# SparkFun_6DoF_ISM330DHCX.net
KiCad netlist of a schematic drawn in EAGLE
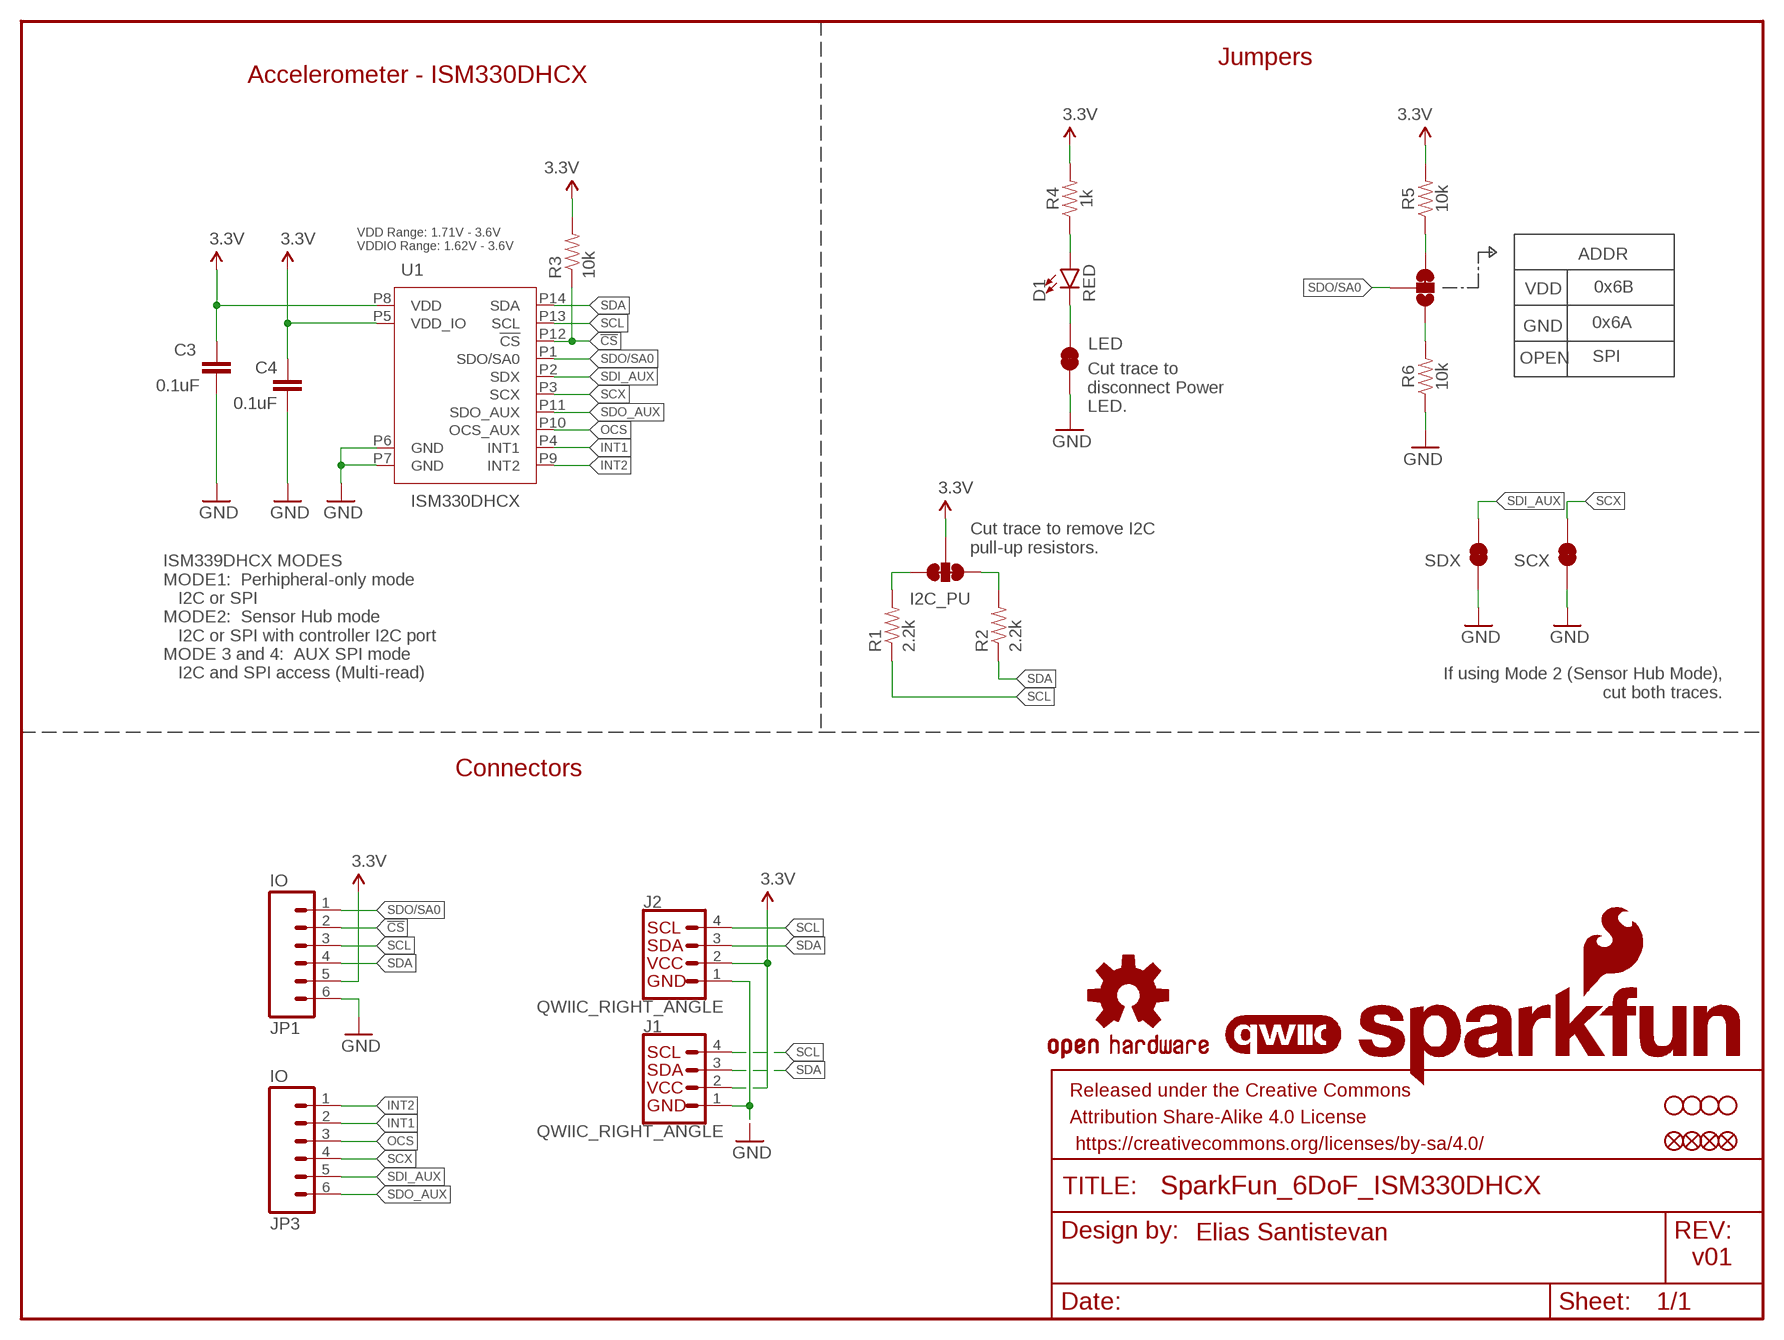
[diagram p0: schematic, sheet 1]

(export (version "E")
  (design (tool "Eeschema 10.0.6"))
  (components
    (comp (ref "ADDR")
      (value "JUMPER-SMT_3_1-NC_TRACE_SILK")
      (footprint "eagle-import:SMT-JUMPER_3_1-NC_TRACE_SILK")
      (libsource (lib "eagle-import") (part "JUMPER-SMT_3_1-NC_TRACE_SILK"))
    )
    (comp (ref "C3")
      (value "0.1uF")
      (footprint "eagle-import:0603")
      (libsource (lib "eagle-import") (part "0.1UF-0603-25V-(+80/-20%)"))
    )
    (comp (ref "C4")
      (value "0.1uF")
      (footprint "eagle-import:0603")
      (libsource (lib "eagle-import") (part "0.1UF-0603-25V-(+80/-20%)"))
    )
    (comp (ref "D1")
      (value "RED")
      (footprint "eagle-import:LED-0603")
      (libsource (lib "eagle-import") (part "LED-RED0603"))
    )
    (comp (ref "FD1")
      (value "FIDUCIALUFIDUCIAL")
      (footprint "eagle-import:FIDUCIAL-MICRO")
      (libsource (lib "eagle-import") (part "FIDUCIALUFIDUCIAL"))
    )
    (comp (ref "FD2")
      (value "FIDUCIALUFIDUCIAL")
      (footprint "eagle-import:FIDUCIAL-MICRO")
      (libsource (lib "eagle-import") (part "FIDUCIALUFIDUCIAL"))
    )
    (comp (ref "FID1")
      (value "FIDUCIALUFIDUCIAL")
      (footprint "eagle-import:FIDUCIAL-MICRO")
      (libsource (lib "eagle-import") (part "FIDUCIALUFIDUCIAL"))
    )
    (comp (ref "FID2")
      (value "FIDUCIALUFIDUCIAL")
      (footprint "eagle-import:FIDUCIAL-MICRO")
      (libsource (lib "eagle-import") (part "FIDUCIALUFIDUCIAL"))
    )
    (comp (ref "FRAME1")
      (value "FRAME-LETTER")
      (footprint "eagle-import:CREATIVE_COMMONS")
      (fields (field (name "DESIGNER") "Elias Santistevan"))
      (libsource (lib "eagle-import") (part "FRAME-LETTER"))
    )
    (comp (ref "I2C_PU")
      (value "S_MODE")
      (footprint "eagle-import:SMT-JUMPER_3_2-NC_TRACE_SILK")
      (libsource (lib "eagle-import") (part "JUMPER-SMT_3_2-NC_TRACE_SILK"))
    )
    (comp (ref "J1")
      (value "QWIIC_RIGHT_ANGLE")
      (footprint "eagle-import:JST04_1MM_RA")
      (libsource (lib "eagle-import") (part "QWIIC_CONNECTORJS-1MM"))
    )
    (comp (ref "J2")
      (value "QWIIC_RIGHT_ANGLE")
      (footprint "eagle-import:JST04_1MM_RA")
      (libsource (lib "eagle-import") (part "QWIIC_CONNECTORJS-1MM"))
    )
    (comp (ref "JP1")
      (value "IO")
      (footprint "eagle-import:1X06_NO_SILK")
      (libsource (lib "eagle-import") (part "CONN_06NO_SILK_NO_POP"))
    )
    (comp (ref "JP3")
      (value "IO")
      (footprint "eagle-import:1X06_NO_SILK")
      (libsource (lib "eagle-import") (part "CONN_06NO_SILK_NO_POP"))
    )
    (comp (ref "LED")
      (value "JUMPER-SMT_2_NC_TRACE_SILK")
      (footprint "eagle-import:SMT-JUMPER_2_NC_TRACE_SILK")
      (libsource (lib "eagle-import") (part "JUMPER-SMT_2_NC_TRACE_SILK"))
    )
    (comp (ref "LOGO1")
      (value "QWIIC_LOGO_4MM")
      (footprint "eagle-import:QWIIC_4MM")
      (libsource (lib "eagle-import") (part "QWIIC_LOGO_4MM"))
    )
    (comp (ref "LOGO2")
      (value "OSHW-LOGOMINI")
      (footprint "eagle-import:OSHW-LOGO-MINI")
      (libsource (lib "eagle-import") (part "OSHW-LOGOMINI"))
    )
    (comp (ref "LOGO3")
      (value "SFE_LOGO_NAME_FLAME.1_INCH")
      (footprint "eagle-import:SFE_LOGO_NAME_FLAME_.1")
      (libsource (lib "eagle-import") (part "SFE_LOGO_NAME_FLAME.1_INCH"))
    )
    (comp (ref "R1")
      (value "2.2k")
      (footprint "eagle-import:0603")
      (libsource (lib "eagle-import") (part "2.2KOHM-0603-1/10W-1%"))
    )
    (comp (ref "R2")
      (value "2.2k")
      (footprint "eagle-import:0603")
      (libsource (lib "eagle-import") (part "2.2KOHM-0603-1/10W-1%"))
    )
    (comp (ref "R3")
      (value "10k")
      (footprint "eagle-import:0603")
      (libsource (lib "eagle-import") (part "10KOHM-0603-1/10W-1%"))
    )
    (comp (ref "R4")
      (value "1k")
      (footprint "eagle-import:0603")
      (libsource (lib "eagle-import") (part "1KOHM-0603-1/10W-1%"))
    )
    (comp (ref "R5")
      (value "10k")
      (footprint "eagle-import:0603")
      (libsource (lib "eagle-import") (part "10KOHM-0603-1/10W-1%"))
    )
    (comp (ref "R6")
      (value "10k")
      (footprint "eagle-import:0603")
      (libsource (lib "eagle-import") (part "10KOHM-0603-1/10W-1%"))
    )
    (comp (ref "SCX")
      (value "JUMPER-SMT_2_NC_TRACE_SILK")
      (footprint "eagle-import:SMT-JUMPER_2_NC_TRACE_SILK")
      (libsource (lib "eagle-import") (part "JUMPER-SMT_2_NC_TRACE_SILK"))
    )
    (comp (ref "SDX")
      (value "JUMPER-SMT_2_NC_TRACE_SILK")
      (footprint "eagle-import:SMT-JUMPER_2_NC_TRACE_SILK")
      (libsource (lib "eagle-import") (part "JUMPER-SMT_2_NC_TRACE_SILK"))
    )
    (comp (ref "STANDOFF1")
      (value "STAND-OFFTIGHT")
      (footprint "eagle-import:STAND-OFF-TIGHT")
      (libsource (lib "eagle-import") (part "STAND-OFFTIGHT"))
    )
    (comp (ref "STANDOFF2")
      (value "STAND-OFFTIGHT")
      (footprint "eagle-import:STAND-OFF-TIGHT")
      (libsource (lib "eagle-import") (part "STAND-OFFTIGHT"))
    )
    (comp (ref "STANDOFF3")
      (value "STAND-OFFTIGHT")
      (footprint "eagle-import:STAND-OFF-TIGHT")
      (libsource (lib "eagle-import") (part "STAND-OFFTIGHT"))
    )
    (comp (ref "STANDOFF4")
      (value "STAND-OFFTIGHT")
      (footprint "eagle-import:STAND-OFF-TIGHT")
      (libsource (lib "eagle-import") (part "STAND-OFFTIGHT"))
    )
    (comp (ref "U1")
      (value "ISM330DHCX")
      (footprint "eagle-import:LGA-14L")
      (libsource (lib "eagle-import") (part "ISM330DHCX"))
    )
  )
  (nets
    (net (code "1") (name "/~{CS}") (class "Default")
      (node (ref "JP1") (pin "2") (pinfunction "2_2") (pintype "passive"))
      (node (ref "R3") (pin "1") (pinfunction "1_1") (pintype "passive"))
      (node (ref "U1") (pin "P12") (pinfunction "~{CS}_P12") (pintype "bidirectional"))
    )
    (net (code "2") (name "3.3V") (class "Default")
      (node (ref "C3") (pin "1") (pinfunction "1_1") (pintype "passive"))
      (node (ref "C4") (pin "1") (pinfunction "1_1") (pintype "passive"))
      (node (ref "I2C_PU") (pin "2") (pinfunction "2_2") (pintype "passive"))
      (node (ref "J1") (pin "2") (pinfunction "2_2") (pintype "power_in"))
      (node (ref "J2") (pin "2") (pinfunction "2_2") (pintype "power_in"))
      (node (ref "JP1") (pin "5") (pinfunction "5_5") (pintype "passive"))
      (node (ref "R3") (pin "2") (pinfunction "2_2") (pintype "passive"))
      (node (ref "R4") (pin "2") (pinfunction "2_2") (pintype "passive"))
      (node (ref "R5") (pin "2") (pinfunction "2_2") (pintype "passive"))
      (node (ref "U1") (pin "P5") (pinfunction "VDD_IO_P5") (pintype "power_in"))
      (node (ref "U1") (pin "P8") (pinfunction "VDD_P8") (pintype "power_in"))
    )
    (net (code "3") (name "GND") (class "Default")
      (node (ref "C3") (pin "2") (pinfunction "2_2") (pintype "passive"))
      (node (ref "C4") (pin "2") (pinfunction "2_2") (pintype "passive"))
      (node (ref "J1") (pin "1") (pinfunction "1_1") (pintype "power_in"))
      (node (ref "J2") (pin "1") (pinfunction "1_1") (pintype "power_in"))
      (node (ref "JP1") (pin "6") (pinfunction "6_6") (pintype "passive"))
      (node (ref "LED") (pin "1") (pinfunction "1_1") (pintype "passive"))
      (node (ref "R6") (pin "1") (pinfunction "1_1") (pintype "passive"))
      (node (ref "SCX") (pin "1") (pinfunction "1_1") (pintype "passive"))
      (node (ref "SDX") (pin "1") (pinfunction "1_1") (pintype "passive"))
      (node (ref "U1") (pin "P6") (pinfunction "GND_P6") (pintype "power_in"))
      (node (ref "U1") (pin "P7") (pinfunction "GND_P7") (pintype "power_in"))
    )
    (net (code "4") (name "INT1") (class "Default")
      (node (ref "JP3") (pin "2") (pinfunction "2_2") (pintype "passive"))
      (node (ref "U1") (pin "P4") (pinfunction "INT1_P4") (pintype "bidirectional"))
    )
    (net (code "5") (name "INT2") (class "Default")
      (node (ref "JP3") (pin "1") (pinfunction "1_1") (pintype "passive"))
      (node (ref "U1") (pin "P9") (pinfunction "INT2_P9") (pintype "bidirectional"))
    )
    (net (code "6") (name "Net-(ADDR-Pad1)") (class "Default")
      (node (ref "ADDR") (pin "1") (pinfunction "1_1") (pintype "passive"))
      (node (ref "R6") (pin "2") (pinfunction "2_2") (pintype "passive"))
    )
    (net (code "7") (name "Net-(ADDR-Pad3)") (class "Default")
      (node (ref "ADDR") (pin "3") (pinfunction "3_3") (pintype "passive"))
      (node (ref "R5") (pin "1") (pinfunction "1_1") (pintype "passive"))
    )
    (net (code "8") (name "Net-(D1-PadA)") (class "Default")
      (node (ref "D1") (pin "A") (pinfunction "A_A") (pintype "passive"))
      (node (ref "R4") (pin "1") (pinfunction "1_1") (pintype "passive"))
    )
    (net (code "9") (name "Net-(D1-PadC)") (class "Default")
      (node (ref "D1") (pin "C") (pinfunction "C_C") (pintype "passive"))
      (node (ref "LED") (pin "2") (pinfunction "2_2") (pintype "passive"))
    )
    (net (code "10") (name "Net-(I2C_PU-Pad1)") (class "Default")
      (node (ref "I2C_PU") (pin "1") (pinfunction "1_1") (pintype "passive"))
      (node (ref "R1") (pin "2") (pinfunction "2_2") (pintype "passive"))
    )
    (net (code "11") (name "Net-(I2C_PU-Pad3)") (class "Default")
      (node (ref "I2C_PU") (pin "3") (pinfunction "3_3") (pintype "passive"))
      (node (ref "R2") (pin "2") (pinfunction "2_2") (pintype "passive"))
    )
    (net (code "12") (name "OCS") (class "Default")
      (node (ref "JP3") (pin "3") (pinfunction "3_3") (pintype "passive"))
      (node (ref "U1") (pin "P10") (pinfunction "OCS_AUX_P10") (pintype "bidirectional"))
    )
    (net (code "13") (name "SCL") (class "Default")
      (node (ref "J1") (pin "4") (pinfunction "4_4") (pintype "passive"))
      (node (ref "J2") (pin "4") (pinfunction "4_4") (pintype "passive"))
      (node (ref "JP1") (pin "3") (pinfunction "3_3") (pintype "passive"))
      (node (ref "R1") (pin "1") (pinfunction "1_1") (pintype "passive"))
      (node (ref "U1") (pin "P13") (pinfunction "SCL_P13") (pintype "bidirectional"))
    )
    (net (code "14") (name "SCX") (class "Default")
      (node (ref "JP3") (pin "4") (pinfunction "4_4") (pintype "passive"))
      (node (ref "SCX") (pin "2") (pinfunction "2_2") (pintype "passive"))
      (node (ref "U1") (pin "P3") (pinfunction "SCX_P3") (pintype "bidirectional"))
    )
    (net (code "15") (name "SDA") (class "Default")
      (node (ref "J1") (pin "3") (pinfunction "3_3") (pintype "passive"))
      (node (ref "J2") (pin "3") (pinfunction "3_3") (pintype "passive"))
      (node (ref "JP1") (pin "4") (pinfunction "4_4") (pintype "passive"))
      (node (ref "R2") (pin "1") (pinfunction "1_1") (pintype "passive"))
      (node (ref "U1") (pin "P14") (pinfunction "SDA_P14") (pintype "bidirectional"))
    )
    (net (code "16") (name "SDI_AUX") (class "Default")
      (node (ref "JP3") (pin "5") (pinfunction "5_5") (pintype "passive"))
      (node (ref "SDX") (pin "2") (pinfunction "2_2") (pintype "passive"))
      (node (ref "U1") (pin "P2") (pinfunction "SDX_P2") (pintype "bidirectional"))
    )
    (net (code "17") (name "SDO_AUX") (class "Default")
      (node (ref "JP3") (pin "6") (pinfunction "6_6") (pintype "passive"))
      (node (ref "U1") (pin "P11") (pinfunction "SDO_AUX_P11") (pintype "bidirectional"))
    )
    (net (code "18") (name "SDO{slash}SA0") (class "Default")
      (node (ref "ADDR") (pin "2") (pinfunction "2_2") (pintype "passive"))
      (node (ref "JP1") (pin "1") (pinfunction "1_1") (pintype "passive"))
      (node (ref "U1") (pin "P1") (pinfunction "SDO/SA0_P1") (pintype "bidirectional"))
    )
  )
)
